# USB2_0.net
KiCad netlist of a schematic drawn in Altium Designer
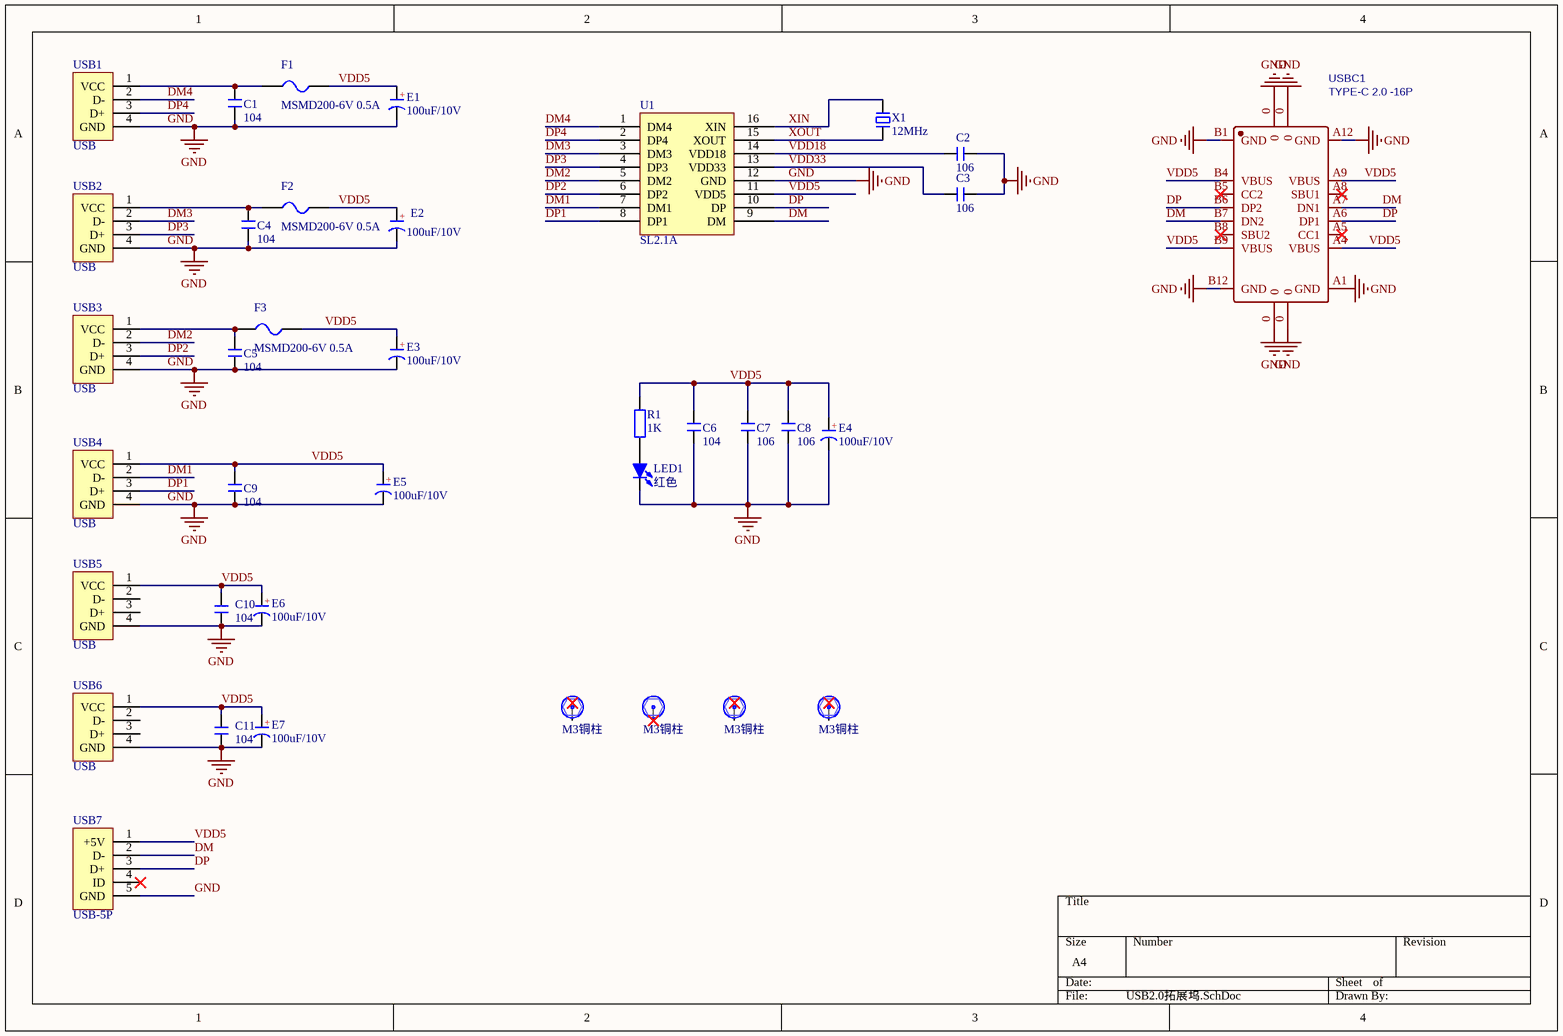
[diagram p0: USB2.0拓展坞.SchDoc]

(export (version "E")
  (design (tool "Eeschema 10.0.6"))
  (components
    (comp (ref "1")
      (value "M3铜柱")
      (footprint "M3x4_L")
      (description "铜柱")
      (fields (field (name "版权归属") "封装库来自淘宝 ID：黄晶宝石"))
      (libsource (lib "4.1 - 未分类器件") (part "铜柱小焊盘"))
    )
    (comp (ref "2")
      (value "M3铜柱")
      (footprint "M3x4_L")
      (description "铜柱")
      (fields (field (name "版权归属") "封装库来自淘宝 ID：黄晶宝石"))
      (libsource (lib "4.1 - 未分类器件") (part "铜柱小焊盘"))
    )
    (comp (ref "3")
      (value "M3铜柱")
      (footprint "M3x4_L")
      (description "铜柱")
      (fields (field (name "版权归属") "封装库来自淘宝 ID：黄晶宝石"))
      (libsource (lib "4.1 - 未分类器件") (part "铜柱小焊盘"))
    )
    (comp (ref "4")
      (value "M3铜柱")
      (footprint "M3x4_L")
      (description "铜柱")
      (fields (field (name "版权归属") "封装库来自淘宝 ID：黄晶宝石"))
      (libsource (lib "4.1 - 未分类器件") (part "铜柱小焊盘"))
    )
    (comp (ref "C1")
      (value "104")
      (footprint "C 0603_L")
      (description "贴片电容")
      (libsource (lib "0.1 - 电阻-电容-电感") (part "C"))
    )
    (comp (ref "C2")
      (value "106")
      (footprint "C 0603_L")
      (description "贴片电容")
      (libsource (lib "0.1 - 电阻-电容-电感") (part "C"))
    )
    (comp (ref "C3")
      (value "106")
      (footprint "C 0603_L")
      (description "贴片电容")
      (libsource (lib "0.1 - 电阻-电容-电感") (part "C"))
    )
    (comp (ref "C4")
      (value "104")
      (footprint "C 0603_L")
      (description "贴片电容")
      (libsource (lib "0.1 - 电阻-电容-电感") (part "C"))
    )
    (comp (ref "C5")
      (value "104")
      (footprint "C 0603_L")
      (description "贴片电容")
      (libsource (lib "0.1 - 电阻-电容-电感") (part "C"))
    )
    (comp (ref "C6")
      (value "104")
      (footprint "C 0603_L")
      (description "贴片电容")
      (libsource (lib "0.1 - 电阻-电容-电感") (part "C"))
    )
    (comp (ref "C7")
      (value "106")
      (footprint "C 0603_L")
      (description "贴片电容")
      (libsource (lib "0.1 - 电阻-电容-电感") (part "C"))
    )
    (comp (ref "C8")
      (value "106")
      (footprint "C 0603_L")
      (description "贴片电容")
      (libsource (lib "0.1 - 电阻-电容-电感") (part "C"))
    )
    (comp (ref "C9")
      (value "104")
      (footprint "C 0603_L")
      (description "贴片电容")
      (libsource (lib "0.1 - 电阻-电容-电感") (part "C"))
    )
    (comp (ref "C10")
      (value "104")
      (footprint "C 0603_L")
      (description "贴片电容")
      (libsource (lib "0.1 - 电阻-电容-电感") (part "C"))
    )
    (comp (ref "C11")
      (value "104")
      (footprint "C 0603_L")
      (description "贴片电容")
      (libsource (lib "0.1 - 电阻-电容-电感") (part "C"))
    )
    (comp (ref "E1")
      (value "100uF/10V")
      (footprint "CM C(5*5.4)")
      (description "贴片电解电容")
      (fields (field (name "版权归属") "封装库来自淘宝 ID：黄晶宝石"))
      (libsource (lib "0.1 - 电阻-电容-电感") (part "CE_SMD"))
    )
    (comp (ref "E2")
      (value "100uF/10V")
      (footprint "CM C(5*5.4)")
      (description "贴片电解电容")
      (fields (field (name "版权归属") "封装库来自淘宝 ID：黄晶宝石"))
      (libsource (lib "0.1 - 电阻-电容-电感") (part "CE_SMD"))
    )
    (comp (ref "E3")
      (value "100uF/10V")
      (footprint "CM C(5*5.4)")
      (description "贴片电解电容")
      (fields (field (name "版权归属") "封装库来自淘宝 ID：黄晶宝石"))
      (libsource (lib "0.1 - 电阻-电容-电感") (part "CE_SMD"))
    )
    (comp (ref "E4")
      (value "100uF/10V")
      (footprint "CM C(5*5.4)")
      (description "贴片电解电容")
      (fields (field (name "版权归属") "封装库来自淘宝 ID：黄晶宝石"))
      (libsource (lib "0.1 - 电阻-电容-电感") (part "CE_SMD"))
    )
    (comp (ref "E5")
      (value "100uF/10V")
      (footprint "CM C(5*5.4)")
      (description "贴片电解电容")
      (fields (field (name "版权归属") "封装库来自淘宝 ID：黄晶宝石"))
      (libsource (lib "0.1 - 电阻-电容-电感") (part "CE_SMD"))
    )
    (comp (ref "E6")
      (value "100uF/10V")
      (footprint "CM C(5*5.4)")
      (description "贴片电解电容")
      (fields (field (name "版权归属") "封装库来自淘宝 ID：黄晶宝石"))
      (libsource (lib "0.1 - 电阻-电容-电感") (part "CE_SMD"))
    )
    (comp (ref "E7")
      (value "100uF/10V")
      (footprint "CM C(5*5.4)")
      (description "贴片电解电容")
      (fields (field (name "版权归属") "封装库来自淘宝 ID：黄晶宝石"))
      (libsource (lib "0.1 - 电阻-电容-电感") (part "CE_SMD"))
    )
    (comp (ref "F1")
      (value "MSMD200-6V 0.5A")
      (footprint "FU 0603")
      (description "贴片保险丝")
      (fields (field (name "版权归属") "封装库来自淘宝卖家 ID：黄晶宝石"))
      (libsource (lib "2.0 - 保险丝-晶振-光耦") (part "FU"))
    )
    (comp (ref "F2")
      (value "MSMD200-6V 0.5A")
      (footprint "FU 0603")
      (description "贴片保险丝")
      (fields (field (name "版权归属") "封装库来自淘宝卖家 ID：黄晶宝石"))
      (libsource (lib "2.0 - 保险丝-晶振-光耦") (part "FU"))
    )
    (comp (ref "F3")
      (value "MSMD200-6V 0.5A")
      (footprint "FU 0603")
      (description "贴片保险丝")
      (fields (field (name "版权归属") "封装库来自淘宝卖家 ID：黄晶宝石"))
      (libsource (lib "2.0 - 保险丝-晶振-光耦") (part "FU"))
    )
    (comp (ref "LED1")
      (value "红色")
      (footprint "LED 0603R")
      (description "贴片LED")
      (fields (field (name "版权归属") "封装库来自淘宝 ID：黄晶宝石"))
      (libsource (lib "0.3 - LED发光二极管") (part "LED-SMD"))
    )
    (comp (ref "R1")
      (value "1K")
      (footprint "R 0603_L")
      (description "贴片电阻")
      (fields (field (name "版权归属") "来自淘宝 ID：黄晶宝石"))
      (libsource (lib "0.1 - 电阻-电容-电感") (part "R"))
    )
    (comp (ref "U1") (value "SL2.1A") (footprint "SOP16") (libsource (lib "四路扩展坞USB2.0") (part "SL2.1A")))
    (comp (ref "USB1")
      (value "USB")
      (footprint "USB-A/S_A")
      (description "USB-A型母接口")
      (fields (field (name "版权归属") "封装库来自淘宝 ID：黄晶宝石"))
      (libsource (lib "0.8 - 以太网-音频-USB插座") (part "USB-A/S"))
    )
    (comp (ref "USB2")
      (value "USB")
      (footprint "USB-A/S_A")
      (description "USB-A型母接口")
      (fields (field (name "版权归属") "封装库来自淘宝 ID：黄晶宝石"))
      (libsource (lib "0.8 - 以太网-音频-USB插座") (part "USB-A/S"))
    )
    (comp (ref "USB3")
      (value "USB")
      (footprint "USB-A/S_A")
      (description "USB-A型母接口")
      (fields (field (name "版权归属") "封装库来自淘宝 ID：黄晶宝石"))
      (libsource (lib "0.8 - 以太网-音频-USB插座") (part "USB-A/S"))
    )
    (comp (ref "USB4")
      (value "USB")
      (footprint "USB-A/S_A")
      (description "USB-A型母接口")
      (fields (field (name "版权归属") "封装库来自淘宝 ID：黄晶宝石"))
      (libsource (lib "0.8 - 以太网-音频-USB插座") (part "USB-A/S"))
    )
    (comp (ref "USB5")
      (value "USB")
      (footprint "USB-A/S_A")
      (description "USB-A型母接口")
      (fields (field (name "版权归属") "封装库来自淘宝 ID：黄晶宝石"))
      (libsource (lib "0.8 - 以太网-音频-USB插座") (part "USB-A/S"))
    )
    (comp (ref "USB6")
      (value "USB")
      (footprint "USB-A/S_A")
      (description "USB-A型母接口")
      (fields (field (name "版权归属") "封装库来自淘宝 ID：黄晶宝石"))
      (libsource (lib "0.8 - 以太网-音频-USB插座") (part "USB-A/S"))
    )
    (comp (ref "USB7")
      (value "USB-5P")
      (footprint "USB-MICRO_A")
      (description "微型USB母座")
      (libsource (lib "0.8 - 以太网-音频-USB插座") (part "USB-5P"))
    )
    (comp (ref "USBC1")
      (value "TYPE-C 2.0 -16P")
      (footprint "USB-C-SMD_TYPE-C-USB-5")
      (description "USB2.0 Type-C 母座 16Pin")
      (libsource (lib "0.8 - 以太网-音频-USB插座") (part "USB2.0 Type-C 16Pin母座"))
    )
    (comp (ref "X1")
      (value "12MHz")
      (footprint "OSC 5032-2P")
      (description "2脚无源脚晶振")
      (fields (field (name "版权归属") "封装库来自淘宝卖家 ID：黄晶宝石"))
      (libsource (lib "2.0 - 保险丝-晶振-光耦") (part "XTAL-2P"))
    )
  )
  (nets
    (net (code "1") (name "/DM") (class "Default")
      (node (ref "U1") (pin "9") (pinfunction "DM_9") (pintype "passive"))
      (node (ref "USB7") (pin "2") (pinfunction "D-_2") (pintype "passive"))
      (node (ref "USBC1") (pin "A7") (pinfunction "DN1_A7") (pintype "passive"))
      (node (ref "USBC1") (pin "B7") (pinfunction "DN2_B7") (pintype "passive"))
    )
    (net (code "2") (name "/DM1") (class "Default")
      (node (ref "U1") (pin "7") (pinfunction "DM1_7") (pintype "passive"))
      (node (ref "USB4") (pin "2") (pinfunction "D-_2") (pintype "passive"))
    )
    (net (code "3") (name "/DM2") (class "Default")
      (node (ref "U1") (pin "5") (pinfunction "DM2_5") (pintype "passive"))
      (node (ref "USB3") (pin "2") (pinfunction "D-_2") (pintype "passive"))
    )
    (net (code "4") (name "/DM3") (class "Default")
      (node (ref "U1") (pin "3") (pinfunction "DM3_3") (pintype "passive"))
      (node (ref "USB2") (pin "2") (pinfunction "D-_2") (pintype "passive"))
    )
    (net (code "5") (name "/DM4") (class "Default")
      (node (ref "U1") (pin "1") (pinfunction "DM4_1") (pintype "passive"))
      (node (ref "USB1") (pin "2") (pinfunction "D-_2") (pintype "passive"))
    )
    (net (code "6") (name "/DP") (class "Default")
      (node (ref "U1") (pin "10") (pinfunction "DP_10") (pintype "passive"))
      (node (ref "USB7") (pin "3") (pinfunction "D+_3") (pintype "passive"))
      (node (ref "USBC1") (pin "A6") (pinfunction "DP1_A6") (pintype "passive"))
      (node (ref "USBC1") (pin "B6") (pinfunction "DP2_B6") (pintype "passive"))
    )
    (net (code "7") (name "/DP1") (class "Default")
      (node (ref "U1") (pin "8") (pinfunction "DP1_8") (pintype "passive"))
      (node (ref "USB4") (pin "3") (pinfunction "D+_3") (pintype "passive"))
    )
    (net (code "8") (name "/DP2") (class "Default")
      (node (ref "U1") (pin "6") (pinfunction "DP2_6") (pintype "passive"))
      (node (ref "USB3") (pin "3") (pinfunction "D+_3") (pintype "passive"))
    )
    (net (code "9") (name "/DP3") (class "Default")
      (node (ref "U1") (pin "4") (pinfunction "DP3_4") (pintype "passive"))
      (node (ref "USB2") (pin "3") (pinfunction "D+_3") (pintype "passive"))
    )
    (net (code "10") (name "/DP4") (class "Default")
      (node (ref "U1") (pin "2") (pinfunction "DP4_2") (pintype "passive"))
      (node (ref "USB1") (pin "3") (pinfunction "D+_3") (pintype "passive"))
    )
    (net (code "11") (name "/VDD5") (class "Default")
      (node (ref "C10") (pin "2") (pinfunction "2_2") (pintype "passive"))
      (node (ref "C11") (pin "2") (pinfunction "2_2") (pintype "passive"))
      (node (ref "C6") (pin "2") (pinfunction "2_2") (pintype "passive"))
      (node (ref "C7") (pin "1") (pinfunction "1_1") (pintype "passive"))
      (node (ref "C8") (pin "1") (pinfunction "1_1") (pintype "passive"))
      (node (ref "C9") (pin "2") (pinfunction "2_2") (pintype "passive"))
      (node (ref "E1") (pin "1") (pinfunction "A_1") (pintype "passive"))
      (node (ref "E2") (pin "1") (pinfunction "A_1") (pintype "passive"))
      (node (ref "E3") (pin "1") (pinfunction "A_1") (pintype "passive"))
      (node (ref "E4") (pin "1") (pinfunction "A_1") (pintype "passive"))
      (node (ref "E5") (pin "1") (pinfunction "A_1") (pintype "passive"))
      (node (ref "E6") (pin "1") (pinfunction "A_1") (pintype "passive"))
      (node (ref "E7") (pin "1") (pinfunction "A_1") (pintype "passive"))
      (node (ref "F1") (pin "2") (pinfunction "2_2") (pintype "passive"))
      (node (ref "F2") (pin "2") (pinfunction "2_2") (pintype "passive"))
      (node (ref "F3") (pin "2") (pinfunction "2_2") (pintype "passive"))
      (node (ref "R1") (pin "2") (pinfunction "2_2") (pintype "passive"))
      (node (ref "U1") (pin "11") (pinfunction "VDD5_11") (pintype "passive"))
      (node (ref "USB4") (pin "1") (pinfunction "VCC_1") (pintype "passive"))
      (node (ref "USB5") (pin "1") (pinfunction "VCC_1") (pintype "passive"))
      (node (ref "USB6") (pin "1") (pinfunction "VCC_1") (pintype "passive"))
      (node (ref "USB7") (pin "1") (pinfunction "+5V_1") (pintype "passive"))
      (node (ref "USBC1") (pin "A4") (pinfunction "VBUS_A4") (pintype "passive"))
      (node (ref "USBC1") (pin "A9") (pinfunction "VBUS_A9") (pintype "passive"))
      (node (ref "USBC1") (pin "B4") (pinfunction "VBUS_B4") (pintype "passive"))
      (node (ref "USBC1") (pin "B9") (pinfunction "VBUS_B9") (pintype "passive"))
    )
    (net (code "12") (name "/VDD18") (class "Default")
      (node (ref "C2") (pin "2") (pinfunction "2_2") (pintype "passive"))
      (node (ref "U1") (pin "14") (pinfunction "VDD18_14") (pintype "passive"))
    )
    (net (code "13") (name "/VDD33") (class "Default")
      (node (ref "C3") (pin "2") (pinfunction "2_2") (pintype "passive"))
      (node (ref "U1") (pin "13") (pinfunction "VDD33_13") (pintype "passive"))
    )
    (net (code "14") (name "/XIN") (class "Default")
      (node (ref "U1") (pin "16") (pinfunction "XIN_16") (pintype "passive"))
      (node (ref "X1") (pin "2") (pinfunction "2_2") (pintype "passive"))
    )
    (net (code "15") (name "/XOUT") (class "Default")
      (node (ref "U1") (pin "15") (pinfunction "XOUT_15") (pintype "passive"))
      (node (ref "X1") (pin "1") (pinfunction "1_1") (pintype "passive"))
    )
    (net (code "16") (name "GND") (class "Default")
      (node (ref "C1") (pin "1") (pinfunction "1_1") (pintype "passive"))
      (node (ref "C10") (pin "1") (pinfunction "1_1") (pintype "passive"))
      (node (ref "C11") (pin "1") (pinfunction "1_1") (pintype "passive"))
      (node (ref "C2") (pin "1") (pinfunction "1_1") (pintype "passive"))
      (node (ref "C3") (pin "1") (pinfunction "1_1") (pintype "passive"))
      (node (ref "C4") (pin "1") (pinfunction "1_1") (pintype "passive"))
      (node (ref "C5") (pin "2") (pinfunction "2_2") (pintype "passive"))
      (node (ref "C6") (pin "1") (pinfunction "1_1") (pintype "passive"))
      (node (ref "C7") (pin "2") (pinfunction "2_2") (pintype "passive"))
      (node (ref "C8") (pin "2") (pinfunction "2_2") (pintype "passive"))
      (node (ref "C9") (pin "1") (pinfunction "1_1") (pintype "passive"))
      (node (ref "E1") (pin "2") (pinfunction "K_2") (pintype "passive"))
      (node (ref "E2") (pin "2") (pinfunction "K_2") (pintype "passive"))
      (node (ref "E3") (pin "2") (pinfunction "K_2") (pintype "passive"))
      (node (ref "E4") (pin "2") (pinfunction "K_2") (pintype "passive"))
      (node (ref "E5") (pin "2") (pinfunction "K_2") (pintype "passive"))
      (node (ref "E6") (pin "2") (pinfunction "K_2") (pintype "passive"))
      (node (ref "E7") (pin "2") (pinfunction "K_2") (pintype "passive"))
      (node (ref "LED1") (pin "2") (pinfunction "K_2") (pintype "passive"))
      (node (ref "U1") (pin "12") (pinfunction "GND_12") (pintype "passive"))
      (node (ref "USB1") (pin "4") (pinfunction "GND_4") (pintype "passive"))
      (node (ref "USB2") (pin "4") (pinfunction "GND_4") (pintype "passive"))
      (node (ref "USB3") (pin "4") (pinfunction "GND_4") (pintype "passive"))
      (node (ref "USB4") (pin "4") (pinfunction "GND_4") (pintype "passive"))
      (node (ref "USB5") (pin "4") (pinfunction "GND_4") (pintype "passive"))
      (node (ref "USB6") (pin "4") (pinfunction "GND_4") (pintype "passive"))
      (node (ref "USB7") (pin "5") (pinfunction "GND_5") (pintype "passive"))
      (node (ref "USBC1") (pin "0") (pinfunction "0_0") (pintype "passive"))
      (node (ref "USBC1") (pin "A1") (pinfunction "GND_A1") (pintype "passive"))
      (node (ref "USBC1") (pin "A12") (pinfunction "GND_A12") (pintype "passive"))
      (node (ref "USBC1") (pin "B1") (pinfunction "GND_B1") (pintype "passive"))
      (node (ref "USBC1") (pin "B12") (pinfunction "GND_B12") (pintype "passive"))
    )
    (net (code "17") (name "Net-(LED1-A)") (class "Default")
      (node (ref "LED1") (pin "1") (pinfunction "A_1") (pintype "passive"))
      (node (ref "R1") (pin "1") (pinfunction "1_1") (pintype "passive"))
    )
    (net (code "18") (name "Net-(USB1-VCC)") (class "Default")
      (node (ref "C1") (pin "2") (pinfunction "2_2") (pintype "passive"))
      (node (ref "F1") (pin "1") (pinfunction "1_1") (pintype "passive"))
      (node (ref "USB1") (pin "1") (pinfunction "VCC_1") (pintype "passive"))
    )
    (net (code "19") (name "Net-(USB2-VCC)") (class "Default")
      (node (ref "C4") (pin "2") (pinfunction "2_2") (pintype "passive"))
      (node (ref "F2") (pin "1") (pinfunction "1_1") (pintype "passive"))
      (node (ref "USB2") (pin "1") (pinfunction "VCC_1") (pintype "passive"))
    )
    (net (code "20") (name "Net-(USB3-VCC)") (class "Default")
      (node (ref "C5") (pin "1") (pinfunction "1_1") (pintype "passive"))
      (node (ref "F3") (pin "1") (pinfunction "1_1") (pintype "passive"))
      (node (ref "USB3") (pin "1") (pinfunction "VCC_1") (pintype "passive"))
    )
    (net (code "21") (name "unconnected-(1-Pad1)") (class "Default")
      (node (ref "1") (pin "1") (pinfunction "1_1") (pintype "passive"))
    )
    (net (code "22") (name "unconnected-(2-Pad1)") (class "Default")
      (node (ref "2") (pin "1") (pinfunction "1_1") (pintype "passive+no_connect"))
    )
    (net (code "23") (name "unconnected-(3-Pad1)") (class "Default")
      (node (ref "3") (pin "1") (pinfunction "1_1") (pintype "passive"))
    )
    (net (code "24") (name "unconnected-(4-Pad1)") (class "Default")
      (node (ref "4") (pin "1") (pinfunction "1_1") (pintype "passive"))
    )
    (net (code "25") (name "unconnected-(USB5-D+-Pad3)") (class "Default")
      (node (ref "USB5") (pin "3") (pinfunction "D+_3") (pintype "passive"))
    )
    (net (code "26") (name "unconnected-(USB5-D--Pad2)") (class "Default")
      (node (ref "USB5") (pin "2") (pinfunction "D-_2") (pintype "passive"))
    )
    (net (code "27") (name "unconnected-(USB6-D+-Pad3)") (class "Default")
      (node (ref "USB6") (pin "3") (pinfunction "D+_3") (pintype "passive"))
    )
    (net (code "28") (name "unconnected-(USB6-D--Pad2)") (class "Default")
      (node (ref "USB6") (pin "2") (pinfunction "D-_2") (pintype "passive"))
    )
    (net (code "29") (name "unconnected-(USB7-ID-Pad4)") (class "Default")
      (node (ref "USB7") (pin "4") (pinfunction "ID_4") (pintype "passive+no_connect"))
    )
    (net (code "30") (name "unconnected-(USBC1-CC1-PadA5)") (class "Default")
      (node (ref "USBC1") (pin "A5") (pinfunction "CC1_A5") (pintype "passive+no_connect"))
    )
    (net (code "31") (name "unconnected-(USBC1-CC2-PadB5)") (class "Default")
      (node (ref "USBC1") (pin "B5") (pinfunction "CC2_B5") (pintype "passive+no_connect"))
    )
    (net (code "32") (name "unconnected-(USBC1-SBU1-PadA8)") (class "Default")
      (node (ref "USBC1") (pin "A8") (pinfunction "SBU1_A8") (pintype "passive+no_connect"))
    )
    (net (code "33") (name "unconnected-(USBC1-SBU2-PadB8)") (class "Default")
      (node (ref "USBC1") (pin "B8") (pinfunction "SBU2_B8") (pintype "passive+no_connect"))
    )
  )
)
